# CANAvionics.net
KiCad netlist of a schematic drawn in EAGLE
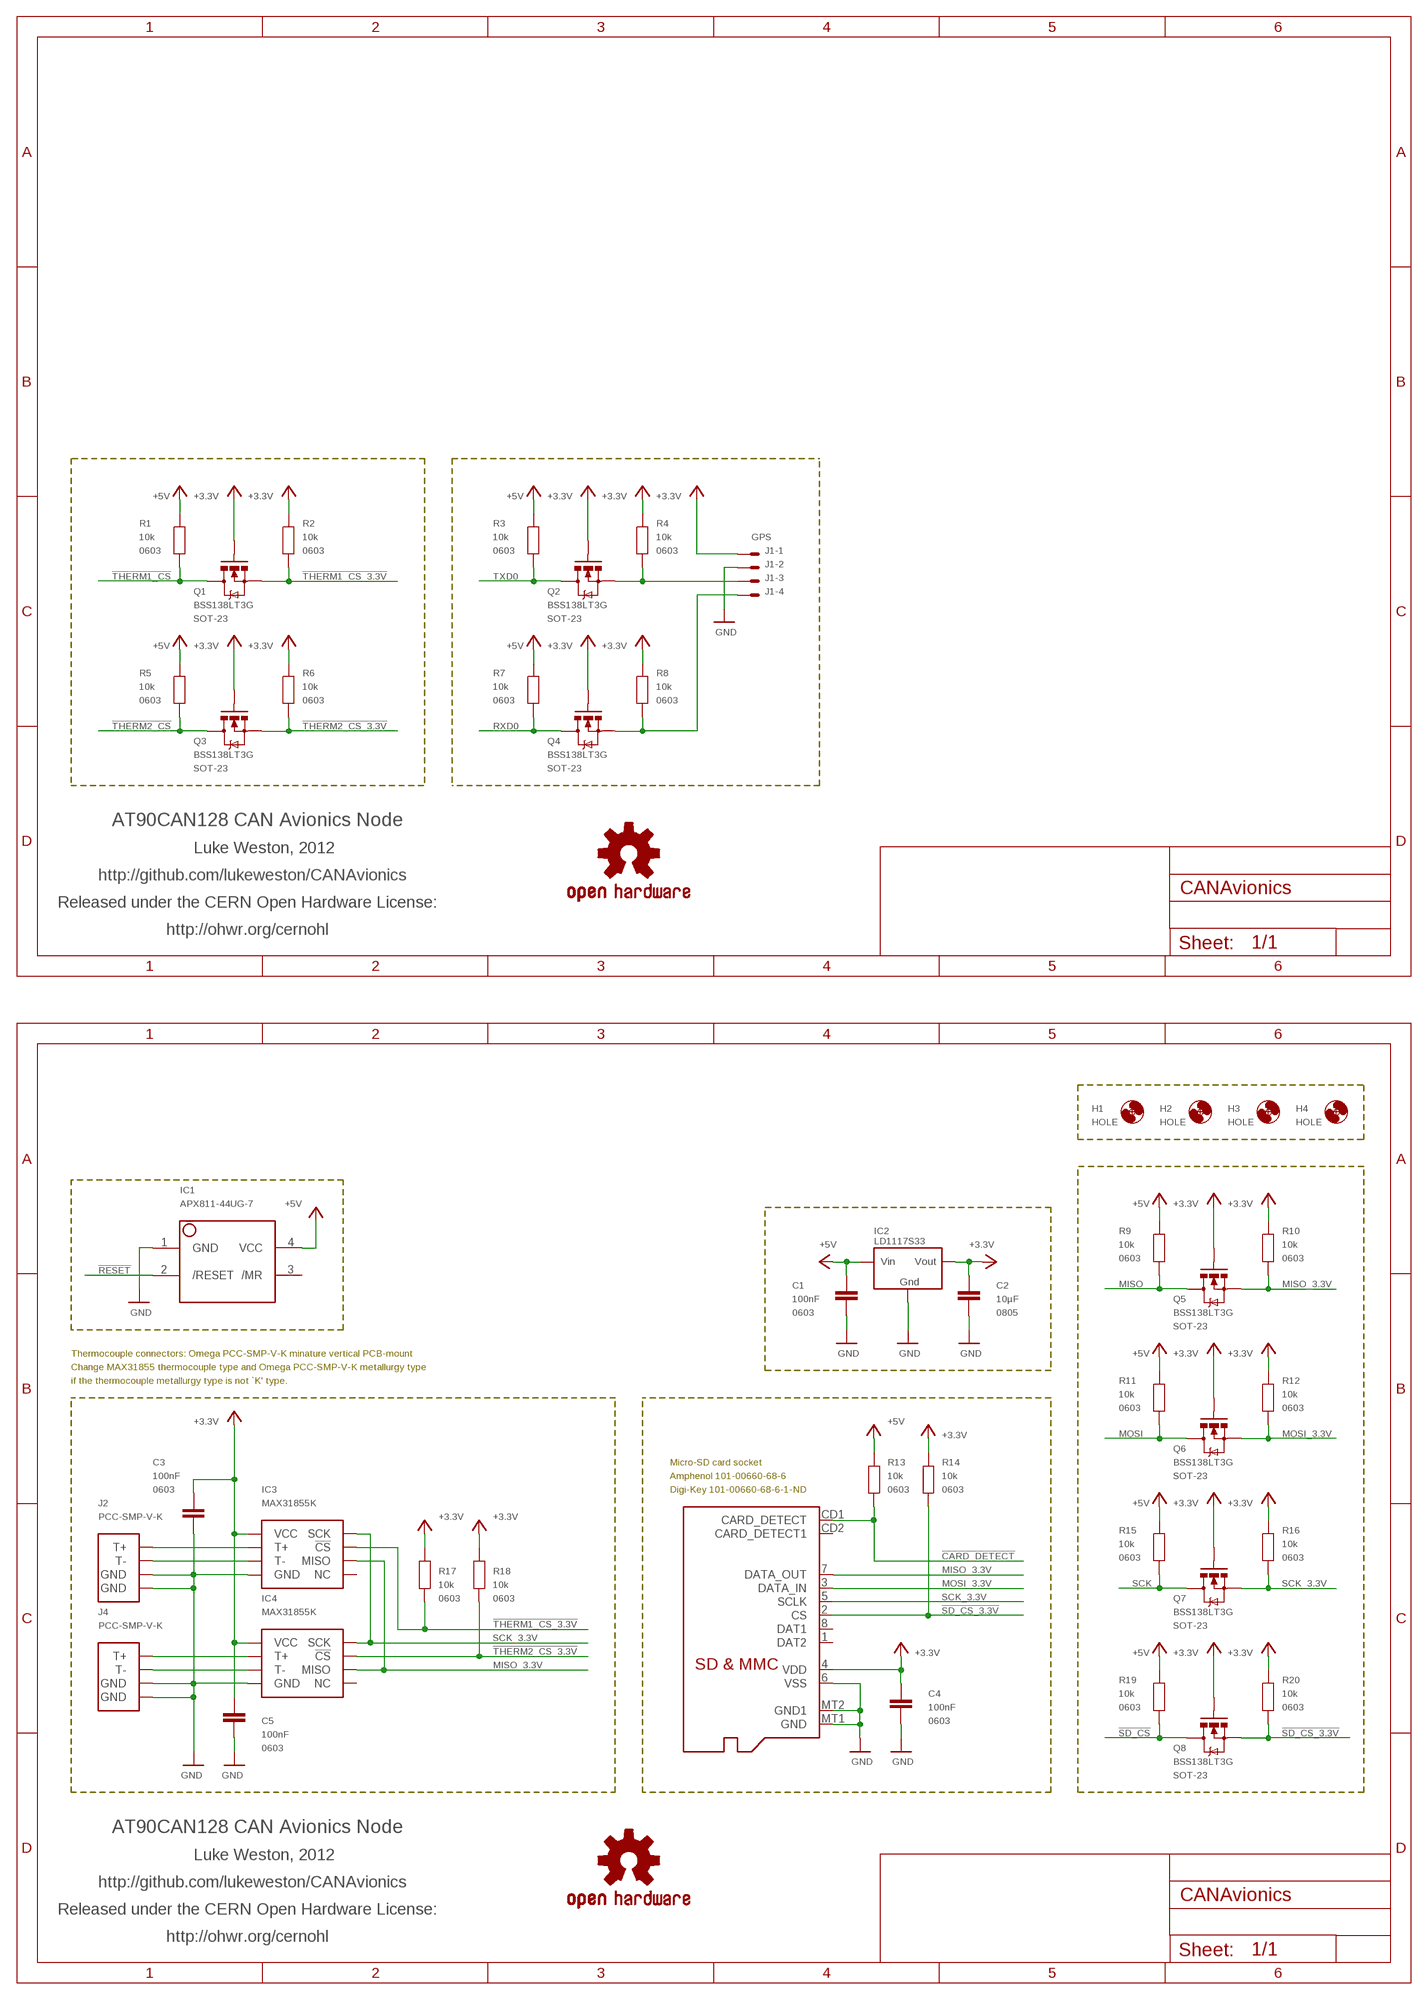
[diagram p0: schematic, sheet 1, part 1 of 2]
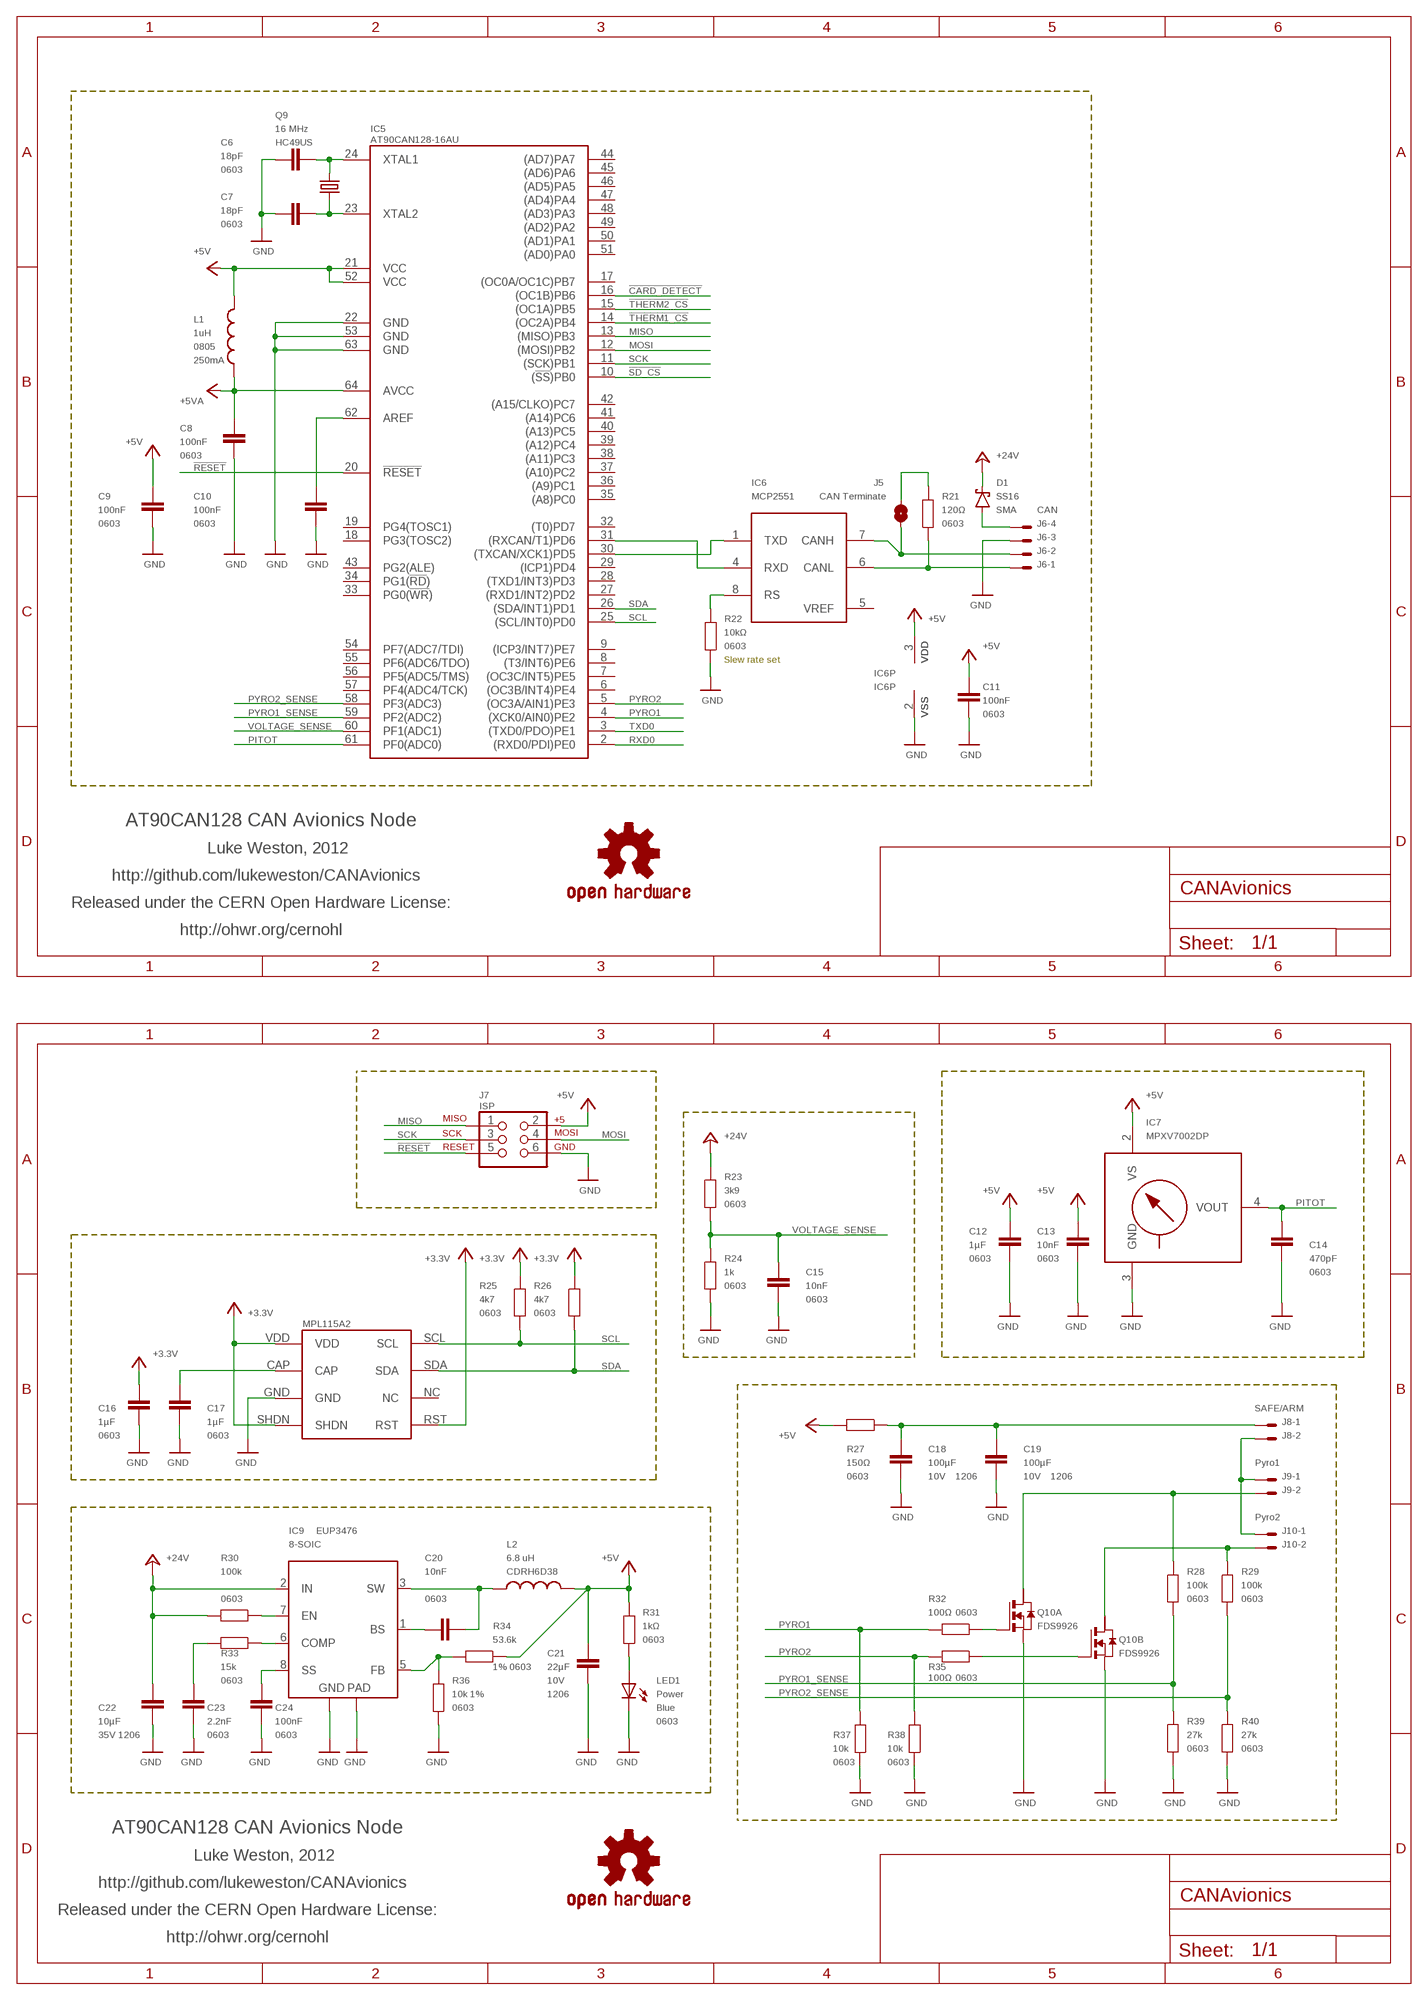
[diagram p1: schematic, sheet 1, part 2 of 2]

(export (version "E")
  (design (tool "Eeschema 10.0.6"))
  (components
    (comp (ref "C1")
      (value "100nF")
      (footprint "eagle-import:0603")
      (fields (field (name "PACKAGE") "0603"))
      (libsource (lib "eagle-import") (part "CAP0603"))
    )
    (comp (ref "C2")
      (value "10µF")
      (footprint "eagle-import:0805")
      (fields (field (name "PACKAGE") "0805"))
      (libsource (lib "eagle-import") (part "CAP0805"))
    )
    (comp (ref "C3")
      (value "100nF")
      (footprint "eagle-import:0603")
      (fields (field (name "PACKAGE") "0603"))
      (libsource (lib "eagle-import") (part "CAP0603"))
    )
    (comp (ref "C4")
      (value "100nF")
      (footprint "eagle-import:0603")
      (fields (field (name "PACKAGE") "0603"))
      (libsource (lib "eagle-import") (part "CAP0603"))
    )
    (comp (ref "C5")
      (value "100nF")
      (footprint "eagle-import:0603")
      (fields (field (name "PACKAGE") "0603"))
      (libsource (lib "eagle-import") (part "CAP0603"))
    )
    (comp (ref "C6")
      (value "18pF")
      (footprint "eagle-import:0603")
      (fields (field (name "PACKAGE") "0603"))
      (libsource (lib "eagle-import") (part "CAP0603"))
    )
    (comp (ref "C7")
      (value "18pF")
      (footprint "eagle-import:0603")
      (fields (field (name "PACKAGE") "0603"))
      (libsource (lib "eagle-import") (part "CAP0603"))
    )
    (comp (ref "C8")
      (value "100nF")
      (footprint "eagle-import:0603")
      (fields (field (name "PACKAGE") "0603"))
      (libsource (lib "eagle-import") (part "CAP0603"))
    )
    (comp (ref "C9")
      (value "100nF")
      (footprint "eagle-import:0603")
      (fields (field (name "PACKAGE") "0603"))
      (libsource (lib "eagle-import") (part "CAP0603"))
    )
    (comp (ref "C10")
      (value "100nF")
      (footprint "eagle-import:0603")
      (fields (field (name "PACKAGE") "0603"))
      (libsource (lib "eagle-import") (part "CAP0603"))
    )
    (comp (ref "C11")
      (value "100nF")
      (footprint "eagle-import:0603")
      (fields (field (name "PACKAGE") "0603"))
      (libsource (lib "eagle-import") (part "CAP0603"))
    )
    (comp (ref "C12")
      (value "1µF")
      (footprint "eagle-import:0603")
      (fields (field (name "PACKAGE") "0603"))
      (libsource (lib "eagle-import") (part "CAP0603"))
    )
    (comp (ref "C13")
      (value "10nF")
      (footprint "eagle-import:0603")
      (fields (field (name "PACKAGE") "0603"))
      (libsource (lib "eagle-import") (part "CAP0603"))
    )
    (comp (ref "C14")
      (value "470pF")
      (footprint "eagle-import:0603")
      (fields (field (name "PACKAGE") "0603"))
      (libsource (lib "eagle-import") (part "CAP0603"))
    )
    (comp (ref "C15")
      (value "10nF")
      (footprint "eagle-import:0603")
      (fields (field (name "PACKAGE") "0603"))
      (libsource (lib "eagle-import") (part "CAP0603"))
    )
    (comp (ref "C16")
      (value "1µF")
      (footprint "eagle-import:0603")
      (fields (field (name "PACKAGE") "0603"))
      (libsource (lib "eagle-import") (part "CAP0603"))
    )
    (comp (ref "C17")
      (value "1µF")
      (footprint "eagle-import:0603")
      (fields (field (name "PACKAGE") "0603"))
      (libsource (lib "eagle-import") (part "CAP0603"))
    )
    (comp (ref "C18")
      (value "100µF")
      (footprint "eagle-import:C1206K")
      (fields (field (name "PACKAGE") "1206") (field (name "VOLTAGE") "10V"))
      (libsource (lib "eagle-import") (part "rcl_C-EUC1206K"))
    )
    (comp (ref "C19")
      (value "100µF")
      (footprint "eagle-import:C1206K")
      (fields (field (name "PACKAGE") "1206") (field (name "VOLTAGE") "10V"))
      (libsource (lib "eagle-import") (part "rcl_C-EUC1206K"))
    )
    (comp (ref "C20")
      (value "10nF")
      (footprint "eagle-import:0603")
      (fields (field (name "PACKAGE") "0603"))
      (libsource (lib "eagle-import") (part "CAP0603"))
    )
    (comp (ref "C21")
      (value "22µF")
      (footprint "eagle-import:C1206K")
      (fields (field (name "PACKAGE") "1206") (field (name "VOLTAGE") "10V"))
      (libsource (lib "eagle-import") (part "C-EUC1206K"))
    )
    (comp (ref "C22")
      (value "10µF")
      (footprint "eagle-import:C1206K")
      (fields (field (name "VOLTAGE") "35V 1206"))
      (libsource (lib "eagle-import") (part "C-EUC1206K"))
    )
    (comp (ref "C23")
      (value "2.2nF")
      (footprint "eagle-import:0603")
      (fields (field (name "PACKAGE") "0603"))
      (libsource (lib "eagle-import") (part "CAP0603"))
    )
    (comp (ref "C24")
      (value "100nF")
      (footprint "eagle-import:0603")
      (fields (field (name "PACKAGE") "0603"))
      (libsource (lib "eagle-import") (part "CAP0603"))
    )
    (comp (ref "D1")
      (value "SS16")
      (footprint "eagle-import:SMA")
      (fields (field (name "PACKAGE") "SMA"))
      (libsource (lib "eagle-import") (part "SCHOTTKY"))
    )
    (comp (ref "H1")
      (value "HOLE")
      (footprint "eagle-import:3,2")
      (libsource (lib "eagle-import") (part "MOUNT-HOLE3.2"))
    )
    (comp (ref "H2")
      (value "HOLE")
      (footprint "eagle-import:3,2")
      (libsource (lib "eagle-import") (part "MOUNT-HOLE3.2"))
    )
    (comp (ref "H3")
      (value "HOLE")
      (footprint "eagle-import:3,2")
      (libsource (lib "eagle-import") (part "MOUNT-HOLE3.2"))
    )
    (comp (ref "H4")
      (value "HOLE")
      (footprint "eagle-import:3,2")
      (libsource (lib "eagle-import") (part "MOUNT-HOLE3.2"))
    )
    (comp (ref "IC1")
      (value "APX811-44UG-7")
      (footprint "eagle-import:SOT143-R")
      (libsource (lib "eagle-import") (part "APX81X-RESET-IC"))
    )
    (comp (ref "IC2")
      (value "LD1117S33")
      (footprint "eagle-import:SOT223")
      (fields (field (name "MPN") "REG1117"))
      (libsource (lib "eagle-import") (part "REG1117"))
    )
    (comp (ref "IC3")
      (value "MAX31855K")
      (footprint "eagle-import:MCLENG_SOIC-8")
      (libsource (lib "eagle-import") (part "MCLENG_MAX6675MAX31855"))
    )
    (comp (ref "IC4")
      (value "MAX31855K")
      (footprint "eagle-import:MCLENG_SOIC-8")
      (libsource (lib "eagle-import") (part "MCLENG_MAX6675MAX31855"))
    )
    (comp (ref "IC5")
      (value "AT90CAN128-16AU")
      (footprint "eagle-import:TQFP64-0.8MM")
      (libsource (lib "eagle-import") (part "AT90CAN128-16AU"))
    )
    (comp (ref "IC6")
      (value "MCP2551")
      (footprint "eagle-import:SO-08")
      (libsource (lib "eagle-import") (part "MCP2551SN"))
    )
    (comp (ref "IC7")
      (value "MPXV7002DP")
      (footprint "eagle-import:1351")
      (libsource (lib "eagle-import") (part "MPXV5004GDP"))
    )
    (comp (ref "IC8")
      (value "MPL115A")
      (footprint "eagle-import:MPL115A")
      (libsource (lib "eagle-import") (part "MPL115A"))
    )
    (comp (ref "IC9")
      (value "EUP3476")
      (footprint "eagle-import:SO08T")
      (fields (field (name "PACKAGE") "8-SOIC"))
      (libsource (lib "eagle-import") (part "EUP3476"))
    )
    (comp (ref "J1")
      (value "GPS")
      (footprint "eagle-import:7395-04")
      (fields (field (name "OC_FARNELL") "unknown") (field (name "OC_NEWARK") "unknown"))
      (libsource (lib "eagle-import") (part "22-?-0405-7048"))
    )
    (comp (ref "J2")
      (value "PCC-SMP-V-K")
      (footprint "eagle-import:MCLAUGHLINENG_TC_JACK")
      (libsource (lib "eagle-import") (part "MCLAUGHLINENG_TC_JACK"))
    )
    (comp (ref "J3")
      (value "MicroSD Card")
      (footprint "eagle-import:ADAFRUIT_MICROSD")
      (libsource (lib "eagle-import") (part "ADAFRUIT_MICROSD"))
    )
    (comp (ref "J4")
      (value "PCC-SMP-V-K")
      (footprint "eagle-import:MCLAUGHLINENG_TC_JACK")
      (libsource (lib "eagle-import") (part "MCLAUGHLINENG_TC_JACK"))
    )
    (comp (ref "J5")
      (value "CAN Terminate")
      (footprint "eagle-import:SJ")
      (libsource (lib "eagle-import") (part "SJ"))
    )
    (comp (ref "J6")
      (value "CAN")
      (footprint "eagle-import:7395-04")
      (libsource (lib "eagle-import") (part "22-?-0405-7048"))
    )
    (comp (ref "J7")
      (value "ISP")
      (footprint "eagle-import:2X3")
      (libsource (lib "eagle-import") (part "AVR_SPI_PRG_6PTH"))
    )
    (comp (ref "J8")
      (value "SAFE/ARM")
      (footprint "eagle-import:7395-02")
      (fields (field (name "OC_FARNELL") "9731601") (field (name "OC_NEWARK") "unknown"))
      (libsource (lib "eagle-import") (part "22-?-0205-7028"))
    )
    (comp (ref "J9")
      (value "Pyro1")
      (footprint "eagle-import:7395-02")
      (libsource (lib "eagle-import") (part "22-?-0205-7028"))
    )
    (comp (ref "J10")
      (value "Pyro2")
      (footprint "eagle-import:7395-02")
      (fields (field (name "OC_FARNELL") "9731601") (field (name "OC_NEWARK") "unknown"))
      (libsource (lib "eagle-import") (part "22-?-0205-7028"))
    )
    (comp (ref "L1")
      (value "1uH")
      (footprint "eagle-import:L2012C")
      (fields (field (name "CURRENT") "250mA") (field (name "PACKAGE") "0805"))
      (libsource (lib "eagle-import") (part "L-USL2012C"))
    )
    (comp (ref "L2")
      (value "6.8 uH")
      (footprint "eagle-import:CDRH")
      (fields (field (name "PACKAGE") "CDRH6D38"))
      (libsource (lib "eagle-import") (part "INDUCTOR"))
    )
    (comp (ref "LED1")
      (value "Power")
      (footprint "eagle-import:LED-0603")
      (fields (field (name "COLOUR") "Blue") (field (name "PACKAGE") "0603"))
      (libsource (lib "eagle-import") (part "LED0603"))
    )
    (comp (ref "Q1")
      (value "BSS138LT3G")
      (footprint "eagle-import:SOT23-3")
      (fields (field (name "PACKAGE") "SOT-23"))
      (libsource (lib "eagle-import") (part "MOSFET-NCHANNELSMD"))
    )
    (comp (ref "Q2")
      (value "BSS138LT3G")
      (footprint "eagle-import:SOT23-3")
      (fields (field (name "PACKAGE") "SOT-23"))
      (libsource (lib "eagle-import") (part "MOSFET-NCHANNELSMD"))
    )
    (comp (ref "Q3")
      (value "BSS138LT3G")
      (footprint "eagle-import:SOT23-3")
      (fields (field (name "PACKAGE") "SOT-23"))
      (libsource (lib "eagle-import") (part "MOSFET-NCHANNELSMD"))
    )
    (comp (ref "Q4")
      (value "BSS138LT3G")
      (footprint "eagle-import:SOT23-3")
      (fields (field (name "PACKAGE") "SOT-23"))
      (libsource (lib "eagle-import") (part "MOSFET-NCHANNELSMD"))
    )
    (comp (ref "Q5")
      (value "BSS138LT3G")
      (footprint "eagle-import:SOT23-3")
      (fields (field (name "PACKAGE") "SOT-23"))
      (libsource (lib "eagle-import") (part "MOSFET-NCHANNELSMD"))
    )
    (comp (ref "Q6")
      (value "BSS138LT3G")
      (footprint "eagle-import:SOT23-3")
      (fields (field (name "PACKAGE") "SOT-23"))
      (libsource (lib "eagle-import") (part "MOSFET-NCHANNELSMD"))
    )
    (comp (ref "Q7")
      (value "BSS138LT3G")
      (footprint "eagle-import:SOT23-3")
      (fields (field (name "PACKAGE") "SOT-23"))
      (libsource (lib "eagle-import") (part "MOSFET-NCHANNELSMD"))
    )
    (comp (ref "Q8")
      (value "BSS138LT3G")
      (footprint "eagle-import:SOT23-3")
      (fields (field (name "PACKAGE") "SOT-23"))
      (libsource (lib "eagle-import") (part "MOSFET-NCHANNELSMD"))
    )
    (comp (ref "Q9")
      (value "16 MHz")
      (footprint "eagle-import:HC49US")
      (fields (field (name "PACKAGE") "HC49US"))
      (libsource (lib "eagle-import") (part "CRYSTALHC49US"))
    )
    (comp (ref "Q10")
      (value "FDS9926")
      (footprint "eagle-import:SM8")
      (libsource (lib "eagle-import") (part "NMOS2SM8"))
    )
    (comp (ref "R1")
      (value "10k")
      (footprint "eagle-import:0603")
      (fields (field (name "PACKAGE") "0603"))
      (libsource (lib "eagle-import") (part "RESISTOR0603"))
    )
    (comp (ref "R2")
      (value "10k")
      (footprint "eagle-import:0603")
      (fields (field (name "PACKAGE") "0603"))
      (libsource (lib "eagle-import") (part "RESISTOR0603"))
    )
    (comp (ref "R3")
      (value "10k")
      (footprint "eagle-import:0603")
      (fields (field (name "PACKAGE") "0603"))
      (libsource (lib "eagle-import") (part "RESISTOR0603"))
    )
    (comp (ref "R4")
      (value "10k")
      (footprint "eagle-import:0603")
      (fields (field (name "PACKAGE") "0603"))
      (libsource (lib "eagle-import") (part "RESISTOR0603"))
    )
    (comp (ref "R5")
      (value "10k")
      (footprint "eagle-import:0603")
      (fields (field (name "PACKAGE") "0603"))
      (libsource (lib "eagle-import") (part "RESISTOR0603"))
    )
    (comp (ref "R6")
      (value "10k")
      (footprint "eagle-import:0603")
      (fields (field (name "PACKAGE") "0603"))
      (libsource (lib "eagle-import") (part "RESISTOR0603"))
    )
    (comp (ref "R7")
      (value "10k")
      (footprint "eagle-import:0603")
      (fields (field (name "PACKAGE") "0603"))
      (libsource (lib "eagle-import") (part "RESISTOR0603"))
    )
    (comp (ref "R8")
      (value "10k")
      (footprint "eagle-import:0603")
      (fields (field (name "PACKAGE") "0603"))
      (libsource (lib "eagle-import") (part "RESISTOR0603"))
    )
    (comp (ref "R9")
      (value "10k")
      (footprint "eagle-import:0603")
      (fields (field (name "PACKAGE") "0603"))
      (libsource (lib "eagle-import") (part "RESISTOR0603"))
    )
    (comp (ref "R10")
      (value "10k")
      (footprint "eagle-import:0603")
      (fields (field (name "PACKAGE") "0603"))
      (libsource (lib "eagle-import") (part "RESISTOR0603"))
    )
    (comp (ref "R11")
      (value "10k")
      (footprint "eagle-import:0603")
      (fields (field (name "PACKAGE") "0603"))
      (libsource (lib "eagle-import") (part "RESISTOR0603"))
    )
    (comp (ref "R12")
      (value "10k")
      (footprint "eagle-import:0603")
      (fields (field (name "PACKAGE") "0603"))
      (libsource (lib "eagle-import") (part "RESISTOR0603"))
    )
    (comp (ref "R13")
      (value "10k")
      (footprint "eagle-import:0603")
      (fields (field (name "PACKAGE") "0603"))
      (libsource (lib "eagle-import") (part "RESISTOR0603"))
    )
    (comp (ref "R14")
      (value "10k")
      (footprint "eagle-import:0603")
      (fields (field (name "PACKAGE") "0603"))
      (libsource (lib "eagle-import") (part "RESISTOR0603"))
    )
    (comp (ref "R15")
      (value "10k")
      (footprint "eagle-import:0603")
      (fields (field (name "PACKAGE") "0603"))
      (libsource (lib "eagle-import") (part "RESISTOR0603"))
    )
    (comp (ref "R16")
      (value "10k")
      (footprint "eagle-import:0603")
      (fields (field (name "PACKAGE") "0603"))
      (libsource (lib "eagle-import") (part "RESISTOR0603"))
    )
    (comp (ref "R17")
      (value "10k")
      (footprint "eagle-import:0603")
      (fields (field (name "PACKAGE") "0603"))
      (libsource (lib "eagle-import") (part "RESISTOR0603"))
    )
    (comp (ref "R18")
      (value "10k")
      (footprint "eagle-import:0603")
      (fields (field (name "PACKAGE") "0603"))
      (libsource (lib "eagle-import") (part "RESISTOR0603"))
    )
    (comp (ref "R19")
      (value "10k")
      (footprint "eagle-import:0603")
      (fields (field (name "PACKAGE") "0603"))
      (libsource (lib "eagle-import") (part "RESISTOR0603"))
    )
    (comp (ref "R20")
      (value "10k")
      (footprint "eagle-import:0603")
      (fields (field (name "PACKAGE") "0603"))
      (libsource (lib "eagle-import") (part "RESISTOR0603"))
    )
    (comp (ref "R21")
      (value "120Ω")
      (footprint "eagle-import:0603")
      (fields (field (name "PACKAGE") "0603"))
      (libsource (lib "eagle-import") (part "RESISTOR0603"))
    )
    (comp (ref "R22")
      (value "10kΩ")
      (footprint "eagle-import:0603")
      (fields (field (name "PACKAGE") "0603"))
      (libsource (lib "eagle-import") (part "RESISTOR0603"))
    )
    (comp (ref "R23")
      (value "3k9")
      (footprint "eagle-import:0603")
      (fields (field (name "PACKAGE") "0603"))
      (libsource (lib "eagle-import") (part "RESISTOR0603"))
    )
    (comp (ref "R24")
      (value "1k")
      (footprint "eagle-import:0603")
      (fields (field (name "PACKAGE") "0603"))
      (libsource (lib "eagle-import") (part "RESISTOR0603"))
    )
    (comp (ref "R25")
      (value "4k7")
      (footprint "eagle-import:0603")
      (fields (field (name "PACKAGE") "0603"))
      (libsource (lib "eagle-import") (part "RESISTOR0603"))
    )
    (comp (ref "R26")
      (value "4k7")
      (footprint "eagle-import:0603")
      (fields (field (name "PACKAGE") "0603"))
      (libsource (lib "eagle-import") (part "RESISTOR0603"))
    )
    (comp (ref "R27")
      (value "150Ω")
      (footprint "eagle-import:0603")
      (fields (field (name "PACKAGE") "0603"))
      (libsource (lib "eagle-import") (part "RESISTOR0603"))
    )
    (comp (ref "R28")
      (value "100k")
      (footprint "eagle-import:0603")
      (fields (field (name "PACKAGE") "0603"))
      (libsource (lib "eagle-import") (part "RESISTOR0603"))
    )
    (comp (ref "R29")
      (value "100k")
      (footprint "eagle-import:0603")
      (fields (field (name "PACKAGE") "0603"))
      (libsource (lib "eagle-import") (part "RESISTOR0603"))
    )
    (comp (ref "R30")
      (value "100k")
      (footprint "eagle-import:0603")
      (fields (field (name "PACKAGE") "0603"))
      (libsource (lib "eagle-import") (part "RESISTOR0603"))
    )
    (comp (ref "R31")
      (value "1kΩ")
      (footprint "eagle-import:0603")
      (fields (field (name "PACKAGE") "0603"))
      (libsource (lib "eagle-import") (part "RESISTOR0603"))
    )
    (comp (ref "R32")
      (value "100Ω")
      (footprint "eagle-import:0603")
      (fields (field (name "PACKAGE") "0603"))
      (libsource (lib "eagle-import") (part "RESISTOR0603"))
    )
    (comp (ref "R33")
      (value "15k")
      (footprint "eagle-import:0603")
      (fields (field (name "PACKAGE") "0603"))
      (libsource (lib "eagle-import") (part "RESISTOR0603"))
    )
    (comp (ref "R34")
      (value "53.6k")
      (footprint "eagle-import:0603")
      (fields (field (name "PACKAGE") "1% 0603"))
      (libsource (lib "eagle-import") (part "RESISTOR0603"))
    )
    (comp (ref "R35")
      (value "100Ω")
      (footprint "eagle-import:0603")
      (fields (field (name "PACKAGE") "0603"))
      (libsource (lib "eagle-import") (part "RESISTOR0603"))
    )
    (comp (ref "R36")
      (value "10k 1%")
      (footprint "eagle-import:0603")
      (fields (field (name "PACKAGE") "0603"))
      (libsource (lib "eagle-import") (part "RESISTOR0603"))
    )
    (comp (ref "R37")
      (value "10k")
      (footprint "eagle-import:0603")
      (fields (field (name "PACKAGE") "0603"))
      (libsource (lib "eagle-import") (part "RESISTOR0603"))
    )
    (comp (ref "R38")
      (value "10k")
      (footprint "eagle-import:0603")
      (fields (field (name "PACKAGE") "0603"))
      (libsource (lib "eagle-import") (part "RESISTOR0603"))
    )
    (comp (ref "R39")
      (value "27k")
      (footprint "eagle-import:0603")
      (fields (field (name "PACKAGE") "0603"))
      (libsource (lib "eagle-import") (part "RESISTOR0603"))
    )
    (comp (ref "R40")
      (value "27k")
      (footprint "eagle-import:0603")
      (fields (field (name "PACKAGE") "0603"))
      (libsource (lib "eagle-import") (part "RESISTOR0603"))
    )
    (comp (ref "SY1")
      (value "OSHW-LOGOS")
      (footprint "eagle-import:OSHW-LOGO-S")
      (libsource (lib "eagle-import") (part "OSHW-LOGOS"))
    )
    (comp (ref "SY2")
      (value "OSHW-LOGOS")
      (footprint "eagle-import:OSHW-LOGO-S")
      (libsource (lib "eagle-import") (part "OSHW-LOGOS"))
    )
    (comp (ref "SY3")
      (value "OSHW-LOGOS")
      (footprint "eagle-import:OSHW-LOGO-S")
      (libsource (lib "eagle-import") (part "OSHW-LOGOS"))
    )
    (comp (ref "SY4")
      (value "OSHW-LOGOS")
      (footprint "eagle-import:OSHW-LOGO-S")
      (libsource (lib "eagle-import") (part "OSHW-LOGOS"))
    )
  )
  (nets
    (net (code "1") (name "+3.3V") (class "Default")
      (node (ref "C16") (pin "2") (pinfunction "2_2") (pintype "passive"))
      (node (ref "C2") (pin "2") (pinfunction "2_2") (pintype "passive"))
      (node (ref "C3") (pin "2") (pinfunction "2_2") (pintype "passive"))
      (node (ref "C4") (pin "2") (pinfunction "2_2") (pintype "passive"))
      (node (ref "C5") (pin "1") (pinfunction "1_1") (pintype "passive"))
      (node (ref "IC2") (pin "2") (pinfunction "VOUT_2") (pintype "output"))
      (node (ref "IC3") (pin "VCC") (pinfunction "VCC_VCC") (pintype "bidirectional"))
      (node (ref "IC4") (pin "VCC") (pinfunction "VCC_VCC") (pintype "bidirectional"))
      (node (ref "IC8") (pin "RST") (pinfunction "RST_RST") (pintype "bidirectional"))
      (node (ref "IC8") (pin "SHDN") (pinfunction "SHDN_SHDN") (pintype "bidirectional"))
      (node (ref "IC8") (pin "VDD") (pinfunction "VDD_VDD") (pintype "bidirectional"))
      (node (ref "J1") (pin "1") (pinfunction "S_1") (pintype "passive"))
      (node (ref "J3") (pin "4") (pinfunction "VDD_4") (pintype "power_in"))
      (node (ref "Q1") (pin "1") (pinfunction "G_1") (pintype "passive"))
      (node (ref "Q2") (pin "1") (pinfunction "G_1") (pintype "passive"))
      (node (ref "Q3") (pin "1") (pinfunction "G_1") (pintype "passive"))
      (node (ref "Q4") (pin "1") (pinfunction "G_1") (pintype "passive"))
      (node (ref "Q5") (pin "1") (pinfunction "G_1") (pintype "passive"))
      (node (ref "Q6") (pin "1") (pinfunction "G_1") (pintype "passive"))
      (node (ref "Q7") (pin "1") (pinfunction "G_1") (pintype "passive"))
      (node (ref "Q8") (pin "1") (pinfunction "G_1") (pintype "passive"))
      (node (ref "R10") (pin "2") (pinfunction "2_2") (pintype "passive"))
      (node (ref "R12") (pin "2") (pinfunction "2_2") (pintype "passive"))
      (node (ref "R14") (pin "1") (pinfunction "1_1") (pintype "passive"))
      (node (ref "R16") (pin "2") (pinfunction "2_2") (pintype "passive"))
      (node (ref "R17") (pin "1") (pinfunction "1_1") (pintype "passive"))
      (node (ref "R18") (pin "1") (pinfunction "1_1") (pintype "passive"))
      (node (ref "R2") (pin "2") (pinfunction "2_2") (pintype "passive"))
      (node (ref "R20") (pin "2") (pinfunction "2_2") (pintype "passive"))
      (node (ref "R25") (pin "2") (pinfunction "2_2") (pintype "passive"))
      (node (ref "R26") (pin "2") (pinfunction "2_2") (pintype "passive"))
      (node (ref "R4") (pin "2") (pinfunction "2_2") (pintype "passive"))
      (node (ref "R6") (pin "2") (pinfunction "2_2") (pintype "passive"))
      (node (ref "R8") (pin "2") (pinfunction "2_2") (pintype "passive"))
    )
    (net (code "2") (name "+5V") (class "Default")
      (node (ref "C1") (pin "2") (pinfunction "2_2") (pintype "passive"))
      (node (ref "C11") (pin "2") (pinfunction "2_2") (pintype "passive"))
      (node (ref "C12") (pin "2") (pinfunction "2_2") (pintype "passive"))
      (node (ref "C13") (pin "2") (pinfunction "2_2") (pintype "passive"))
      (node (ref "C21") (pin "1") (pinfunction "1_1") (pintype "passive"))
      (node (ref "C9") (pin "2") (pinfunction "2_2") (pintype "passive"))
      (node (ref "IC1") (pin "4") (pinfunction "VCC_4") (pintype "power_in"))
      (node (ref "IC2") (pin "3") (pinfunction "VIN_3") (pintype "input"))
      (node (ref "IC5") (pin "21") (pinfunction "VCC_21") (pintype "power_in"))
      (node (ref "IC5") (pin "52") (pinfunction "VCC_52") (pintype "power_in"))
      (node (ref "IC6") (pin "3") (pinfunction "VDD_3") (pintype "power_in"))
      (node (ref "IC7") (pin "2") (pinfunction "VS_2") (pintype "power_in"))
      (node (ref "J7") (pin "2") (pinfunction "2_2") (pintype "passive"))
      (node (ref "L1") (pin "1") (pinfunction "1_1") (pintype "passive"))
      (node (ref "L2") (pin "2") (pinfunction "2_2") (pintype "bidirectional"))
      (node (ref "R1") (pin "2") (pinfunction "2_2") (pintype "passive"))
      (node (ref "R11") (pin "2") (pinfunction "2_2") (pintype "passive"))
      (node (ref "R13") (pin "1") (pinfunction "1_1") (pintype "passive"))
      (node (ref "R15") (pin "2") (pinfunction "2_2") (pintype "passive"))
      (node (ref "R19") (pin "2") (pinfunction "2_2") (pintype "passive"))
      (node (ref "R27") (pin "2") (pinfunction "2_2") (pintype "passive"))
      (node (ref "R3") (pin "2") (pinfunction "2_2") (pintype "passive"))
      (node (ref "R31") (pin "1") (pinfunction "1_1") (pintype "passive"))
      (node (ref "R34") (pin "1") (pinfunction "1_1") (pintype "passive"))
      (node (ref "R5") (pin "2") (pinfunction "2_2") (pintype "passive"))
      (node (ref "R7") (pin "2") (pinfunction "2_2") (pintype "passive"))
      (node (ref "R9") (pin "2") (pinfunction "2_2") (pintype "passive"))
    )
    (net (code "3") (name "+5VA") (class "Default")
      (node (ref "C8") (pin "2") (pinfunction "2_2") (pintype "passive"))
      (node (ref "IC5") (pin "64") (pinfunction "AVCC_64") (pintype "power_in"))
      (node (ref "L1") (pin "2") (pinfunction "2_2") (pintype "passive"))
    )
    (net (code "4") (name "+24V") (class "Default")
      (node (ref "C22") (pin "1") (pinfunction "1_1") (pintype "passive"))
      (node (ref "D1") (pin "K") (pinfunction "K_K") (pintype "passive"))
      (node (ref "IC9") (pin "2") (pinfunction "IN_2") (pintype "power_in"))
      (node (ref "R23") (pin "2") (pinfunction "2_2") (pintype "passive"))
      (node (ref "R30") (pin "2") (pinfunction "2_2") (pintype "passive"))
    )
    (net (code "5") (name "/MISO") (class "Default")
      (node (ref "IC5") (pin "13") (pinfunction "(MISO)PB3_13") (pintype "bidirectional"))
      (node (ref "J7") (pin "1") (pinfunction "1_1") (pintype "passive"))
      (node (ref "Q5") (pin "3") (pinfunction "D_3") (pintype "passive"))
      (node (ref "R9") (pin "1") (pinfunction "1_1") (pintype "passive"))
    )
    (net (code "6") (name "/MISO_3.3V") (class "Default")
      (node (ref "IC3") (pin "SO") (pinfunction "MISO_SO") (pintype "bidirectional"))
      (node (ref "IC4") (pin "SO") (pinfunction "MISO_SO") (pintype "bidirectional"))
      (node (ref "J3") (pin "7") (pinfunction "DATA_OUT_7") (pintype "output"))
      (node (ref "Q5") (pin "2") (pinfunction "S_2") (pintype "passive"))
      (node (ref "R10") (pin "1") (pinfunction "1_1") (pintype "passive"))
    )
    (net (code "7") (name "/MOSI") (class "Default")
      (node (ref "IC5") (pin "12") (pinfunction "(MOSI)PB2_12") (pintype "bidirectional"))
      (node (ref "J7") (pin "4") (pinfunction "4_4") (pintype "passive"))
      (node (ref "Q6") (pin "3") (pinfunction "D_3") (pintype "passive"))
      (node (ref "R11") (pin "1") (pinfunction "1_1") (pintype "passive"))
    )
    (net (code "8") (name "/MOSI_3.3V") (class "Default")
      (node (ref "J3") (pin "3") (pinfunction "DATA_IN_3") (pintype "input"))
      (node (ref "Q6") (pin "2") (pinfunction "S_2") (pintype "passive"))
      (node (ref "R12") (pin "1") (pinfunction "1_1") (pintype "passive"))
    )
    (net (code "9") (name "/PITOT") (class "Default")
      (node (ref "C14") (pin "2") (pinfunction "2_2") (pintype "passive"))
      (node (ref "IC5") (pin "61") (pinfunction "PF0(ADC0)_61") (pintype "bidirectional"))
      (node (ref "IC7") (pin "4") (pinfunction "VOUT_4") (pintype "output"))
    )
    (net (code "10") (name "/PYRO1") (class "Default")
      (node (ref "IC5") (pin "4") (pinfunction "(XCK0/AIN0)PE2_4") (pintype "bidirectional"))
      (node (ref "R32") (pin "2") (pinfunction "2_2") (pintype "passive"))
      (node (ref "R37") (pin "1") (pinfunction "1_1") (pintype "passive"))
    )
    (net (code "11") (name "/PYRO1_SENSE") (class "Default")
      (node (ref "IC5") (pin "59") (pinfunction "PF2(ADC2)_59") (pintype "bidirectional"))
      (node (ref "R28") (pin "1") (pinfunction "1_1") (pintype "passive"))
      (node (ref "R39") (pin "2") (pinfunction "2_2") (pintype "passive"))
    )
    (net (code "12") (name "/PYRO2") (class "Default")
      (node (ref "IC5") (pin "5") (pinfunction "(OC3A/AIN1)PE3_5") (pintype "bidirectional"))
      (node (ref "R35") (pin "2") (pinfunction "2_2") (pintype "passive"))
      (node (ref "R38") (pin "1") (pinfunction "1_1") (pintype "passive"))
    )
    (net (code "13") (name "/PYRO2_SENSE") (class "Default")
      (node (ref "IC5") (pin "58") (pinfunction "PF3(ADC3)_58") (pintype "bidirectional"))
      (node (ref "R29") (pin "1") (pinfunction "1_1") (pintype "passive"))
      (node (ref "R40") (pin "2") (pinfunction "2_2") (pintype "passive"))
    )
    (net (code "14") (name "/RXD0") (class "Default")
      (node (ref "IC5") (pin "2") (pinfunction "(RXD0/PDI)PE0_2") (pintype "bidirectional"))
      (node (ref "Q4") (pin "3") (pinfunction "D_3") (pintype "passive"))
      (node (ref "R7") (pin "1") (pinfunction "1_1") (pintype "passive"))
    )
    (net (code "15") (name "/SCK") (class "Default")
      (node (ref "IC5") (pin "11") (pinfunction "(SCK)PB1_11") (pintype "bidirectional"))
      (node (ref "J7") (pin "3") (pinfunction "3_3") (pintype "passive"))
      (node (ref "Q7") (pin "3") (pinfunction "D_3") (pintype "passive"))
      (node (ref "R15") (pin "1") (pinfunction "1_1") (pintype "passive"))
    )
    (net (code "16") (name "/SCK_3.3V") (class "Default")
      (node (ref "IC3") (pin "SCK") (pinfunction "SCK_SCK") (pintype "bidirectional"))
      (node (ref "IC4") (pin "SCK") (pinfunction "SCK_SCK") (pintype "bidirectional"))
      (node (ref "J3") (pin "5") (pinfunction "SCLK_5") (pintype "input"))
      (node (ref "Q7") (pin "2") (pinfunction "S_2") (pintype "passive"))
      (node (ref "R16") (pin "1") (pinfunction "1_1") (pintype "passive"))
    )
    (net (code "17") (name "/SCL") (class "Default")
      (node (ref "IC5") (pin "25") (pinfunction "(SCL/INT0)PD0_25") (pintype "bidirectional"))
      (node (ref "IC8") (pin "SCL") (pinfunction "SCL_SCL") (pintype "bidirectional"))
      (node (ref "R25") (pin "1") (pinfunction "1_1") (pintype "passive"))
    )
    (net (code "18") (name "/SDA") (class "Default")
      (node (ref "IC5") (pin "26") (pinfunction "(SDA/INT1)PD1_26") (pintype "bidirectional"))
      (node (ref "IC8") (pin "SDA") (pinfunction "SDA_SDA") (pintype "bidirectional"))
      (node (ref "R26") (pin "1") (pinfunction "1_1") (pintype "passive"))
    )
    (net (code "19") (name "/TXD0") (class "Default")
      (node (ref "IC5") (pin "3") (pinfunction "(TXD0/PDO)PE1_3") (pintype "bidirectional"))
      (node (ref "Q2") (pin "3") (pinfunction "D_3") (pintype "passive"))
      (node (ref "R3") (pin "1") (pinfunction "1_1") (pintype "passive"))
    )
    (net (code "20") (name "/VOLTAGE_SENSE") (class "Default")
      (node (ref "C15") (pin "2") (pinfunction "2_2") (pintype "passive"))
      (node (ref "IC5") (pin "60") (pinfunction "PF1(ADC1)_60") (pintype "bidirectional"))
      (node (ref "R23") (pin "1") (pinfunction "1_1") (pintype "passive"))
      (node (ref "R24") (pin "2") (pinfunction "2_2") (pintype "passive"))
    )
    (net (code "21") (name "/VREF") (class "Default")
      (node (ref "IC6") (pin "5") (pinfunction "VREF_5") (pintype "power_in"))
    )
    (net (code "22") (name "/~{CARD_DETECT}") (class "Default")
      (node (ref "IC5") (pin "16") (pinfunction "(OC1B)PB6_16") (pintype "bidirectional"))
      (node (ref "J3") (pin "CD1") (pinfunction "CARD_DETECT_CD1") (pintype "passive"))
      (node (ref "R13") (pin "2") (pinfunction "2_2") (pintype "passive"))
    )
    (net (code "23") (name "/~{RESET}") (class "Default")
      (node (ref "IC1") (pin "2") (pinfunction "/RESET_2") (pintype "output"))
      (node (ref "IC5") (pin "20") (pinfunction "~{RESET}_20") (pintype "input"))
      (node (ref "J7") (pin "5") (pinfunction "5_5") (pintype "passive"))
    )
    (net (code "24") (name "/~{SD_CS_3.3V}") (class "Default")
      (node (ref "J3") (pin "2") (pinfunction "CS_2") (pintype "input"))
      (node (ref "Q8") (pin "2") (pinfunction "S_2") (pintype "passive"))
      (node (ref "R14") (pin "2") (pinfunction "2_2") (pintype "passive"))
      (node (ref "R20") (pin "1") (pinfunction "1_1") (pintype "passive"))
    )
    (net (code "25") (name "/~{SD_CS}") (class "Default")
      (node (ref "IC5") (pin "10") (pinfunction "(~{SS})PB0_10") (pintype "bidirectional"))
      (node (ref "Q8") (pin "3") (pinfunction "D_3") (pintype "passive"))
      (node (ref "R19") (pin "1") (pinfunction "1_1") (pintype "passive"))
    )
    (net (code "26") (name "/~{THERM1_CS_3.3V}") (class "Default")
      (node (ref "IC3") (pin "CS") (pinfunction "~{CS}_CS") (pintype "bidirectional"))
      (node (ref "Q1") (pin "2") (pinfunction "S_2") (pintype "passive"))
      (node (ref "R17") (pin "2") (pinfunction "2_2") (pintype "passive"))
      (node (ref "R2") (pin "1") (pinfunction "1_1") (pintype "passive"))
    )
    (net (code "27") (name "/~{THERM1_CS}") (class "Default")
      (node (ref "IC5") (pin "14") (pinfunction "(OC2A)PB4_14") (pintype "bidirectional"))
      (node (ref "Q1") (pin "3") (pinfunction "D_3") (pintype "passive"))
      (node (ref "R1") (pin "1") (pinfunction "1_1") (pintype "passive"))
    )
    (net (code "28") (name "/~{THERM2_CS_3.3V}") (class "Default")
      (node (ref "IC4") (pin "CS") (pinfunction "~{CS}_CS") (pintype "bidirectional"))
      (node (ref "Q3") (pin "2") (pinfunction "S_2") (pintype "passive"))
      (node (ref "R18") (pin "2") (pinfunction "2_2") (pintype "passive"))
      (node (ref "R6") (pin "1") (pinfunction "1_1") (pintype "passive"))
    )
    (net (code "29") (name "/~{THERM2_CS}") (class "Default")
      (node (ref "IC5") (pin "15") (pinfunction "(OC1A)PB5_15") (pintype "bidirectional"))
      (node (ref "Q3") (pin "3") (pinfunction "D_3") (pintype "passive"))
      (node (ref "R5") (pin "1") (pinfunction "1_1") (pintype "passive"))
    )
    (net (code "30") (name "GND") (class "Default")
      (node (ref "C1") (pin "1") (pinfunction "1_1") (pintype "passive"))
      (node (ref "C10") (pin "1") (pinfunction "1_1") (pintype "passive"))
      (node (ref "C11") (pin "1") (pinfunction "1_1") (pintype "passive"))
      (node (ref "C12") (pin "1") (pinfunction "1_1") (pintype "passive"))
      (node (ref "C13") (pin "1") (pinfunction "1_1") (pintype "passive"))
      (node (ref "C14") (pin "1") (pinfunction "1_1") (pintype "passive"))
      (node (ref "C15") (pin "1") (pinfunction "1_1") (pintype "passive"))
      (node (ref "C16") (pin "1") (pinfunction "1_1") (pintype "passive"))
      (node (ref "C17") (pin "1") (pinfunction "1_1") (pintype "passive"))
      (node (ref "C18") (pin "1") (pinfunction "1_1") (pintype "passive"))
      (node (ref "C19") (pin "1") (pinfunction "1_1") (pintype "passive"))
      (node (ref "C2") (pin "1") (pinfunction "1_1") (pintype "passive"))
      (node (ref "C21") (pin "2") (pinfunction "2_2") (pintype "passive"))
      (node (ref "C22") (pin "2") (pinfunction "2_2") (pintype "passive"))
      (node (ref "C23") (pin "1") (pinfunction "1_1") (pintype "passive"))
      (node (ref "C24") (pin "1") (pinfunction "1_1") (pintype "passive"))
      (node (ref "C3") (pin "1") (pinfunction "1_1") (pintype "passive"))
      (node (ref "C4") (pin "1") (pinfunction "1_1") (pintype "passive"))
      (node (ref "C5") (pin "2") (pinfunction "2_2") (pintype "passive"))
      (node (ref "C6") (pin "1") (pinfunction "1_1") (pintype "passive"))
      (node (ref "C7") (pin "1") (pinfunction "1_1") (pintype "passive"))
      (node (ref "C8") (pin "1") (pinfunction "1_1") (pintype "passive"))
      (node (ref "C9") (pin "1") (pinfunction "1_1") (pintype "passive"))
      (node (ref "IC1") (pin "1") (pinfunction "GND_1") (pintype "power_in"))
      (node (ref "IC2") (pin "1") (pinfunction "GND_1") (pintype "power_in"))
      (node (ref "IC3") (pin "GND") (pinfunction "GND_GND") (pintype "bidirectional"))
      (node (ref "IC4") (pin "GND") (pinfunction "GND_GND") (pintype "bidirectional"))
      (node (ref "IC5") (pin "22") (pinfunction "GND_22") (pintype "power_in"))
      (node (ref "IC5") (pin "53") (pinfunction "GND_53") (pintype "power_in"))
      (node (ref "IC5") (pin "63") (pinfunction "GND_63") (pintype "power_in"))
      (node (ref "IC6") (pin "2") (pinfunction "VSS_2") (pintype "power_in"))
      (node (ref "IC7") (pin "3") (pinfunction "GND_3") (pintype "power_in"))
      (node (ref "IC8") (pin "GND") (pinfunction "GND_GND") (pintype "bidirectional"))
      (node (ref "IC9") (pin "4") (pinfunction "GND_4") (pintype "power_in"))
      (node (ref "IC9") (pin "9") (pinfunction "TGND_9") (pintype "power_in"))
      (node (ref "J1") (pin "2") (pinfunction "S_2") (pintype "passive"))
      (node (ref "J2") (pin "P$1") (pinfunction "GND_P$1") (pintype "bidirectional"))
      (node (ref "J2") (pin "P$2") (pinfunction "GND_P$2") (pintype "bidirectional"))
      (node (ref "J3") (pin "6") (pinfunction "VSS_6") (pintype "power_in"))
      (node (ref "J3") (pin "MT1") (pinfunction "GND_MT1") (pintype "power_in"))
      (node (ref "J3") (pin "MT2") (pinfunction "GND1_MT2") (pintype "power_in"))
      (node (ref "J4") (pin "P$1") (pinfunction "GND_P$1") (pintype "bidirectional"))
      (node (ref "J4") (pin "P$2") (pinfunction "GND_P$2") (pintype "bidirectional"))
      (node (ref "J6") (pin "3") (pinfunction "S_3") (pintype "passive"))
      (node (ref "J7") (pin "6") (pinfunction "6_6") (pintype "passive"))
      (node (ref "LED1") (pin "C") (pinfunction "C_C") (pintype "passive"))
      (node (ref "Q10") (pin "1") (pinfunction "S_1") (pintype "passive"))
      (node (ref "Q10") (pin "3") (pinfunction "S_3") (pintype "passive"))
      (node (ref "R22") (pin "2") (pinfunction "2_2") (pintype "passive"))
      (node (ref "R24") (pin "1") (pinfunction "1_1") (pintype "passive"))
      (node (ref "R36") (pin "2") (pinfunction "2_2") (pintype "passive"))
      (node (ref "R37") (pin "2") (pinfunction "2_2") (pintype "passive"))
      (node (ref "R38") (pin "2") (pinfunction "2_2") (pintype "passive"))
      (node (ref "R39") (pin "1") (pinfunction "1_1") (pintype "passive"))
      (node (ref "R40") (pin "1") (pinfunction "1_1") (pintype "passive"))
    )
    (net (code "31") (name "Net-(C17-Pad2)") (class "Default")
      (node (ref "C17") (pin "2") (pinfunction "2_2") (pintype "passive"))
      (node (ref "IC8") (pin "CAP") (pinfunction "CAP_CAP") (pintype "bidirectional"))
    )
    (net (code "32") (name "Net-(C23-Pad2)") (class "Default")
      (node (ref "C23") (pin "2") (pinfunction "2_2") (pintype "passive"))
      (node (ref "R33") (pin "2") (pinfunction "2_2") (pintype "passive"))
    )
    (net (code "33") (name "Net-(IC3-PadT+)") (class "Default")
      (node (ref "IC3") (pin "T+") (pinfunction "T+_T+") (pintype "bidirectional"))
      (node (ref "J2") (pin "T+") (pinfunction "T+_T+") (pintype "bidirectional"))
    )
    (net (code "34") (name "Net-(IC3-PadT-)") (class "Default")
      (node (ref "IC3") (pin "T-") (pinfunction "T-_T-") (pintype "bidirectional"))
      (node (ref "J2") (pin "T-") (pinfunction "T-_T-") (pintype "bidirectional"))
    )
    (net (code "35") (name "Net-(IC4-PadT+)") (class "Default")
      (node (ref "IC4") (pin "T+") (pinfunction "T+_T+") (pintype "bidirectional"))
      (node (ref "J4") (pin "T+") (pinfunction "T+_T+") (pintype "bidirectional"))
    )
    (net (code "36") (name "Net-(IC4-PadT-)") (class "Default")
      (node (ref "IC4") (pin "T-") (pinfunction "T-_T-") (pintype "bidirectional"))
      (node (ref "J4") (pin "T-") (pinfunction "T-_T-") (pintype "bidirectional"))
    )
    (net (code "37") (name "Net-(IC5-(RXCAN{slash}T1)PD6)") (class "Default")
      (node (ref "IC5") (pin "31") (pinfunction "(RXCAN/T1)PD6_31") (pintype "bidirectional"))
      (node (ref "IC6") (pin "4") (pinfunction "RXD_4") (pintype "output"))
    )
    (net (code "38") (name "Net-(IC5-(TXCAN{slash}XCK1)PD5)") (class "Default")
      (node (ref "IC5") (pin "30") (pinfunction "(TXCAN/XCK1)PD5_30") (pintype "bidirectional"))
      (node (ref "IC6") (pin "1") (pinfunction "TXD_1") (pintype "input"))
    )
    (net (code "39") (name "Net-(IC5-AREF)") (class "Default")
      (node (ref "C10") (pin "2") (pinfunction "2_2") (pintype "passive"))
      (node (ref "IC5") (pin "62") (pinfunction "AREF_62") (pintype "passive"))
    )
    (net (code "40") (name "Net-(IC5-XTAL1)") (class "Default")
      (node (ref "C6") (pin "2") (pinfunction "2_2") (pintype "passive"))
      (node (ref "IC5") (pin "24") (pinfunction "XTAL1_24") (pintype "passive"))
      (node (ref "Q9") (pin "2") (pinfunction "2_2") (pintype "passive"))
    )
    (net (code "41") (name "Net-(IC5-XTAL2)") (class "Default")
      (node (ref "C7") (pin "2") (pinfunction "2_2") (pintype "passive"))
      (node (ref "IC5") (pin "23") (pinfunction "XTAL2_23") (pintype "passive"))
      (node (ref "Q9") (pin "1") (pinfunction "1_1") (pintype "passive"))
    )
    (net (code "42") (name "Net-(IC6A-CANH)") (class "Default")
      (node (ref "IC6") (pin "7") (pinfunction "CANH_7") (pintype "bidirectional"))
      (node (ref "J5") (pin "2") (pinfunction "2_2") (pintype "passive"))
      (node (ref "J6") (pin "2") (pinfunction "S_2") (pintype "passive"))
    )
    (net (code "43") (name "Net-(IC6A-CANL)") (class "Default")
      (node (ref "IC6") (pin "6") (pinfunction "CANL_6") (pintype "bidirectional"))
      (node (ref "J6") (pin "1") (pinfunction "S_1") (pintype "passive"))
      (node (ref "R21") (pin "1") (pinfunction "1_1") (pintype "passive"))
    )
    (net (code "44") (name "Net-(IC6A-RS)") (class "Default")
      (node (ref "IC6") (pin "8") (pinfunction "RS_8") (pintype "input"))
      (node (ref "R22") (pin "1") (pinfunction "1_1") (pintype "passive"))
    )
    (net (code "45") (name "Net-(IC9-BS)") (class "Default")
      (node (ref "C20") (pin "2") (pinfunction "2_2") (pintype "passive"))
      (node (ref "IC9") (pin "1") (pinfunction "BS_1") (pintype "bidirectional"))
    )
    (net (code "46") (name "Net-(IC9-COMP)") (class "Default")
      (node (ref "IC9") (pin "6") (pinfunction "COMP_6") (pintype "bidirectional"))
      (node (ref "R33") (pin "1") (pinfunction "1_1") (pintype "passive"))
    )
    (net (code "47") (name "Net-(IC9-EN)") (class "Default")
      (node (ref "IC9") (pin "7") (pinfunction "EN_7") (pintype "input"))
      (node (ref "R30") (pin "1") (pinfunction "1_1") (pintype "passive"))
    )
    (net (code "48") (name "Net-(IC9-FB)") (class "Default")
      (node (ref "IC9") (pin "5") (pinfunction "FB_5") (pintype "bidirectional"))
      (node (ref "R34") (pin "2") (pinfunction "2_2") (pintype "passive"))
      (node (ref "R36") (pin "1") (pinfunction "1_1") (pintype "passive"))
    )
    (net (code "49") (name "Net-(IC9-SS)") (class "Default")
      (node (ref "C24") (pin "2") (pinfunction "2_2") (pintype "passive"))
      (node (ref "IC9") (pin "8") (pinfunction "SS_8") (pintype "bidirectional"))
    )
    (net (code "50") (name "Net-(IC9-SW)") (class "Default")
      (node (ref "C20") (pin "1") (pinfunction "1_1") (pintype "passive"))
      (node (ref "IC9") (pin "3") (pinfunction "SW_3") (pintype "bidirectional"))
      (node (ref "L2") (pin "1") (pinfunction "1_1") (pintype "bidirectional"))
    )
    (net (code "51") (name "Net-(J1C-S)") (class "Default")
      (node (ref "J1") (pin "3") (pinfunction "S_3") (pintype "passive"))
      (node (ref "Q2") (pin "2") (pinfunction "S_2") (pintype "passive"))
      (node (ref "R4") (pin "1") (pinfunction "1_1") (pintype "passive"))
    )
    (net (code "52") (name "Net-(J1D-S)") (class "Default")
      (node (ref "J1") (pin "4") (pinfunction "S_4") (pintype "passive"))
      (node (ref "Q4") (pin "2") (pinfunction "S_2") (pintype "passive"))
      (node (ref "R8") (pin "1") (pinfunction "1_1") (pintype "passive"))
    )
    (net (code "53") (name "Net-(J5-Pad1)") (class "Default")
      (node (ref "J5") (pin "1") (pinfunction "1_1") (pintype "passive"))
      (node (ref "R21") (pin "2") (pinfunction "2_2") (pintype "passive"))
    )
    (net (code "54") (name "Net-(J6D-S)") (class "Default")
      (node (ref "D1") (pin "A") (pinfunction "A_A") (pintype "passive"))
      (node (ref "J6") (pin "4") (pinfunction "S_4") (pintype "passive"))
    )
    (net (code "55") (name "Net-(J8A-S)") (class "Default")
      (node (ref "C18") (pin "2") (pinfunction "2_2") (pintype "passive"))
      (node (ref "C19") (pin "2") (pinfunction "2_2") (pintype "passive"))
      (node (ref "J8") (pin "1") (pinfunction "S_1") (pintype "passive"))
      (node (ref "R27") (pin "1") (pinfunction "1_1") (pintype "passive"))
    )
    (net (code "56") (name "Net-(J9B-S)") (class "Default")
      (node (ref "J9") (pin "2") (pinfunction "S_2") (pintype "passive"))
      (node (ref "Q10") (pin "5") (pinfunction "D_5") (pintype "passive"))
      (node (ref "R28") (pin "2") (pinfunction "2_2") (pintype "passive"))
    )
    (net (code "57") (name "Net-(J10A-S)") (class "Default")
      (node (ref "J10") (pin "1") (pinfunction "S_1") (pintype "passive"))
      (node (ref "J8") (pin "2") (pinfunction "S_2") (pintype "passive"))
      (node (ref "J9") (pin "1") (pinfunction "S_1") (pintype "passive"))
    )
    (net (code "58") (name "Net-(J10B-S)") (class "Default")
      (node (ref "J10") (pin "2") (pinfunction "S_2") (pintype "passive"))
      (node (ref "Q10") (pin "7") (pinfunction "D_7") (pintype "passive"))
      (node (ref "R29") (pin "2") (pinfunction "2_2") (pintype "passive"))
    )
    (net (code "59") (name "Net-(LED1-PadA)") (class "Default")
      (node (ref "LED1") (pin "A") (pinfunction "A_A") (pintype "passive"))
      (node (ref "R31") (pin "2") (pinfunction "2_2") (pintype "passive"))
    )
    (net (code "60") (name "Net-(Q10A-G)") (class "Default")
      (node (ref "Q10") (pin "4") (pinfunction "G_4") (pintype "passive"))
      (node (ref "R32") (pin "1") (pinfunction "1_1") (pintype "passive"))
    )
    (net (code "61") (name "Net-(Q10B-G)") (class "Default")
      (node (ref "Q10") (pin "2") (pinfunction "G_2") (pintype "passive"))
      (node (ref "R35") (pin "1") (pinfunction "1_1") (pintype "passive"))
    )
    (net (code "62") (name "unconnected-(IC1-{slash}MR-Pad3)") (class "Default")
      (node (ref "IC1") (pin "3") (pinfunction "/MR_3") (pintype "input"))
    )
    (net (code "63") (name "unconnected-(IC3-PadNC)") (class "Default")
      (node (ref "IC3") (pin "NC") (pinfunction "NC_NC") (pintype "no_connect"))
    )
    (net (code "64") (name "unconnected-(IC4-PadNC)") (class "Default")
      (node (ref "IC4") (pin "NC") (pinfunction "NC_NC") (pintype "no_connect"))
    )
    (net (code "65") (name "unconnected-(IC5-(A8)PC0-Pad35)") (class "Default")
      (node (ref "IC5") (pin "35") (pinfunction "(A8)PC0_35") (pintype "bidirectional"))
    )
    (net (code "66") (name "unconnected-(IC5-(A9)PC1-Pad36)") (class "Default")
      (node (ref "IC5") (pin "36") (pinfunction "(A9)PC1_36") (pintype "bidirectional"))
    )
    (net (code "67") (name "unconnected-(IC5-(A10)PC2-Pad37)") (class "Default")
      (node (ref "IC5") (pin "37") (pinfunction "(A10)PC2_37") (pintype "bidirectional"))
    )
    (net (code "68") (name "unconnected-(IC5-(A11)PC3-Pad38)") (class "Default")
      (node (ref "IC5") (pin "38") (pinfunction "(A11)PC3_38") (pintype "bidirectional"))
    )
    (net (code "69") (name "unconnected-(IC5-(A12)PC4-Pad39)") (class "Default")
      (node (ref "IC5") (pin "39") (pinfunction "(A12)PC4_39") (pintype "bidirectional"))
    )
    (net (code "70") (name "unconnected-(IC5-(A13)PC5-Pad40)") (class "Default")
      (node (ref "IC5") (pin "40") (pinfunction "(A13)PC5_40") (pintype "bidirectional"))
    )
    (net (code "71") (name "unconnected-(IC5-(A14)PC6-Pad41)") (class "Default")
      (node (ref "IC5") (pin "41") (pinfunction "(A14)PC6_41") (pintype "bidirectional"))
    )
    (net (code "72") (name "unconnected-(IC5-(A15{slash}CLKO)PC7-Pad42)") (class "Default")
      (node (ref "IC5") (pin "42") (pinfunction "(A15/CLKO)PC7_42") (pintype "bidirectional"))
    )
    (net (code "73") (name "unconnected-(IC5-(AD0)PA0-Pad51)") (class "Default")
      (node (ref "IC5") (pin "51") (pinfunction "(AD0)PA0_51") (pintype "bidirectional"))
    )
    (net (code "74") (name "unconnected-(IC5-(AD1)PA1-Pad50)") (class "Default")
      (node (ref "IC5") (pin "50") (pinfunction "(AD1)PA1_50") (pintype "bidirectional"))
    )
    (net (code "75") (name "unconnected-(IC5-(AD2)PA2-Pad49)") (class "Default")
      (node (ref "IC5") (pin "49") (pinfunction "(AD2)PA2_49") (pintype "bidirectional"))
    )
    (net (code "76") (name "unconnected-(IC5-(AD3)PA3-Pad48)") (class "Default")
      (node (ref "IC5") (pin "48") (pinfunction "(AD3)PA3_48") (pintype "bidirectional"))
    )
    (net (code "77") (name "unconnected-(IC5-(AD4)PA4-Pad47)") (class "Default")
      (node (ref "IC5") (pin "47") (pinfunction "(AD4)PA4_47") (pintype "bidirectional"))
    )
    (net (code "78") (name "unconnected-(IC5-(AD5)PA5-Pad46)") (class "Default")
      (node (ref "IC5") (pin "46") (pinfunction "(AD5)PA5_46") (pintype "bidirectional"))
    )
    (net (code "79") (name "unconnected-(IC5-(AD6)PA6-Pad45)") (class "Default")
      (node (ref "IC5") (pin "45") (pinfunction "(AD6)PA6_45") (pintype "bidirectional"))
    )
    (net (code "80") (name "unconnected-(IC5-(AD7)PA7-Pad44)") (class "Default")
      (node (ref "IC5") (pin "44") (pinfunction "(AD7)PA7_44") (pintype "bidirectional"))
    )
    (net (code "81") (name "unconnected-(IC5-(ICP1)PD4-Pad29)") (class "Default")
      (node (ref "IC5") (pin "29") (pinfunction "(ICP1)PD4_29") (pintype "bidirectional"))
    )
    (net (code "82") (name "unconnected-(IC5-(ICP3{slash}INT7)PE7-Pad9)") (class "Default")
      (node (ref "IC5") (pin "9") (pinfunction "(ICP3/INT7)PE7_9") (pintype "bidirectional"))
    )
    (net (code "83") (name "unconnected-(IC5-(OC0A{slash}OC1C)PB7-Pad17)") (class "Default")
      (node (ref "IC5") (pin "17") (pinfunction "(OC0A/OC1C)PB7_17") (pintype "bidirectional"))
    )
    (net (code "84") (name "unconnected-(IC5-(OC3B{slash}INT4)PE4-Pad6)") (class "Default")
      (node (ref "IC5") (pin "6") (pinfunction "(OC3B/INT4)PE4_6") (pintype "bidirectional"))
    )
    (net (code "85") (name "unconnected-(IC5-(OC3C{slash}INT5)PE5-Pad7)") (class "Default")
      (node (ref "IC5") (pin "7") (pinfunction "(OC3C/INT5)PE5_7") (pintype "bidirectional"))
    )
    (net (code "86") (name "unconnected-(IC5-(RXD1{slash}INT2)PD2-Pad27)") (class "Default")
      (node (ref "IC5") (pin "27") (pinfunction "(RXD1/INT2)PD2_27") (pintype "bidirectional"))
    )
    (net (code "87") (name "unconnected-(IC5-(T0)PD7-Pad32)") (class "Default")
      (node (ref "IC5") (pin "32") (pinfunction "(T0)PD7_32") (pintype "bidirectional"))
    )
    (net (code "88") (name "unconnected-(IC5-(T3{slash}INT6)PE6-Pad8)") (class "Default")
      (node (ref "IC5") (pin "8") (pinfunction "(T3/INT6)PE6_8") (pintype "bidirectional"))
    )
    (net (code "89") (name "unconnected-(IC5-(TXD1{slash}INT3)PD3-Pad28)") (class "Default")
      (node (ref "IC5") (pin "28") (pinfunction "(TXD1/INT3)PD3_28") (pintype "bidirectional"))
    )
    (net (code "90") (name "unconnected-(IC5-PF4(ADC4{slash}TCK)-Pad57)") (class "Default")
      (node (ref "IC5") (pin "57") (pinfunction "PF4(ADC4/TCK)_57") (pintype "bidirectional"))
    )
    (net (code "91") (name "unconnected-(IC5-PF5(ADC5{slash}TMS)-Pad56)") (class "Default")
      (node (ref "IC5") (pin "56") (pinfunction "PF5(ADC5/TMS)_56") (pintype "bidirectional"))
    )
    (net (code "92") (name "unconnected-(IC5-PF6(ADC6{slash}TDO)-Pad55)") (class "Default")
      (node (ref "IC5") (pin "55") (pinfunction "PF6(ADC6/TDO)_55") (pintype "bidirectional"))
    )
    (net (code "93") (name "unconnected-(IC5-PF7(ADC7{slash}TDI)-Pad54)") (class "Default")
      (node (ref "IC5") (pin "54") (pinfunction "PF7(ADC7/TDI)_54") (pintype "bidirectional"))
    )
    (net (code "94") (name "unconnected-(IC5-PG0(~{WR})-Pad33)") (class "Default")
      (node (ref "IC5") (pin "33") (pinfunction "PG0(~{WR})_33") (pintype "bidirectional"))
    )
    (net (code "95") (name "unconnected-(IC5-PG1(~{RD})-Pad34)") (class "Default")
      (node (ref "IC5") (pin "34") (pinfunction "PG1(~{RD})_34") (pintype "bidirectional"))
    )
    (net (code "96") (name "unconnected-(IC5-PG2(ALE)-Pad43)") (class "Default")
      (node (ref "IC5") (pin "43") (pinfunction "PG2(ALE)_43") (pintype "bidirectional"))
    )
    (net (code "97") (name "unconnected-(IC5-PG3(TOSC2)-Pad18)") (class "Default")
      (node (ref "IC5") (pin "18") (pinfunction "PG3(TOSC2)_18") (pintype "bidirectional"))
    )
    (net (code "98") (name "unconnected-(IC5-PG4(TOSC1)-Pad19)") (class "Default")
      (node (ref "IC5") (pin "19") (pinfunction "PG4(TOSC1)_19") (pintype "bidirectional"))
    )
    (net (code "99") (name "unconnected-(IC7-NC-Pad1)") (class "Default")
      (node (ref "IC7") (pin "1") (pinfunction "NC_1") (pintype "no_connect"))
    )
    (net (code "100") (name "unconnected-(IC7-NC-Pad5)") (class "Default")
      (node (ref "IC7") (pin "5") (pinfunction "NC_5") (pintype "no_connect"))
    )
    (net (code "101") (name "unconnected-(IC7-NC-Pad6)") (class "Default")
      (node (ref "IC7") (pin "6") (pinfunction "NC_6") (pintype "no_connect"))
    )
    (net (code "102") (name "unconnected-(IC8-PadNC)") (class "Default")
      (node (ref "IC8") (pin "NC") (pinfunction "NC_NC") (pintype "bidirectional"))
    )
    (net (code "103") (name "unconnected-(J3-CARD_DETECT1-PadCD2)") (class "Default")
      (node (ref "J3") (pin "CD2") (pinfunction "CARD_DETECT1_CD2") (pintype "passive"))
    )
    (net (code "104") (name "unconnected-(J3-DAT1-Pad8)") (class "Default")
      (node (ref "J3") (pin "8") (pinfunction "DAT1_8") (pintype "bidirectional"))
    )
    (net (code "105") (name "unconnected-(J3-DAT2-Pad1)") (class "Default")
      (node (ref "J3") (pin "1") (pinfunction "DAT2_1") (pintype "bidirectional"))
    )
    (net (code "106") (name "unconnected-(Q10A-D2-Pad6)") (class "Default")
      (node (ref "Q10") (pin "6") (pinfunction "D2_6") (pintype "passive"))
    )
    (net (code "107") (name "unconnected-(Q10B-D2-Pad8)") (class "Default")
      (node (ref "Q10") (pin "8") (pinfunction "D2_8") (pintype "passive"))
    )
  )
)
